# MOSFET_killswitch.net
KiCad netlist of a schematic drawn in Altium Designer
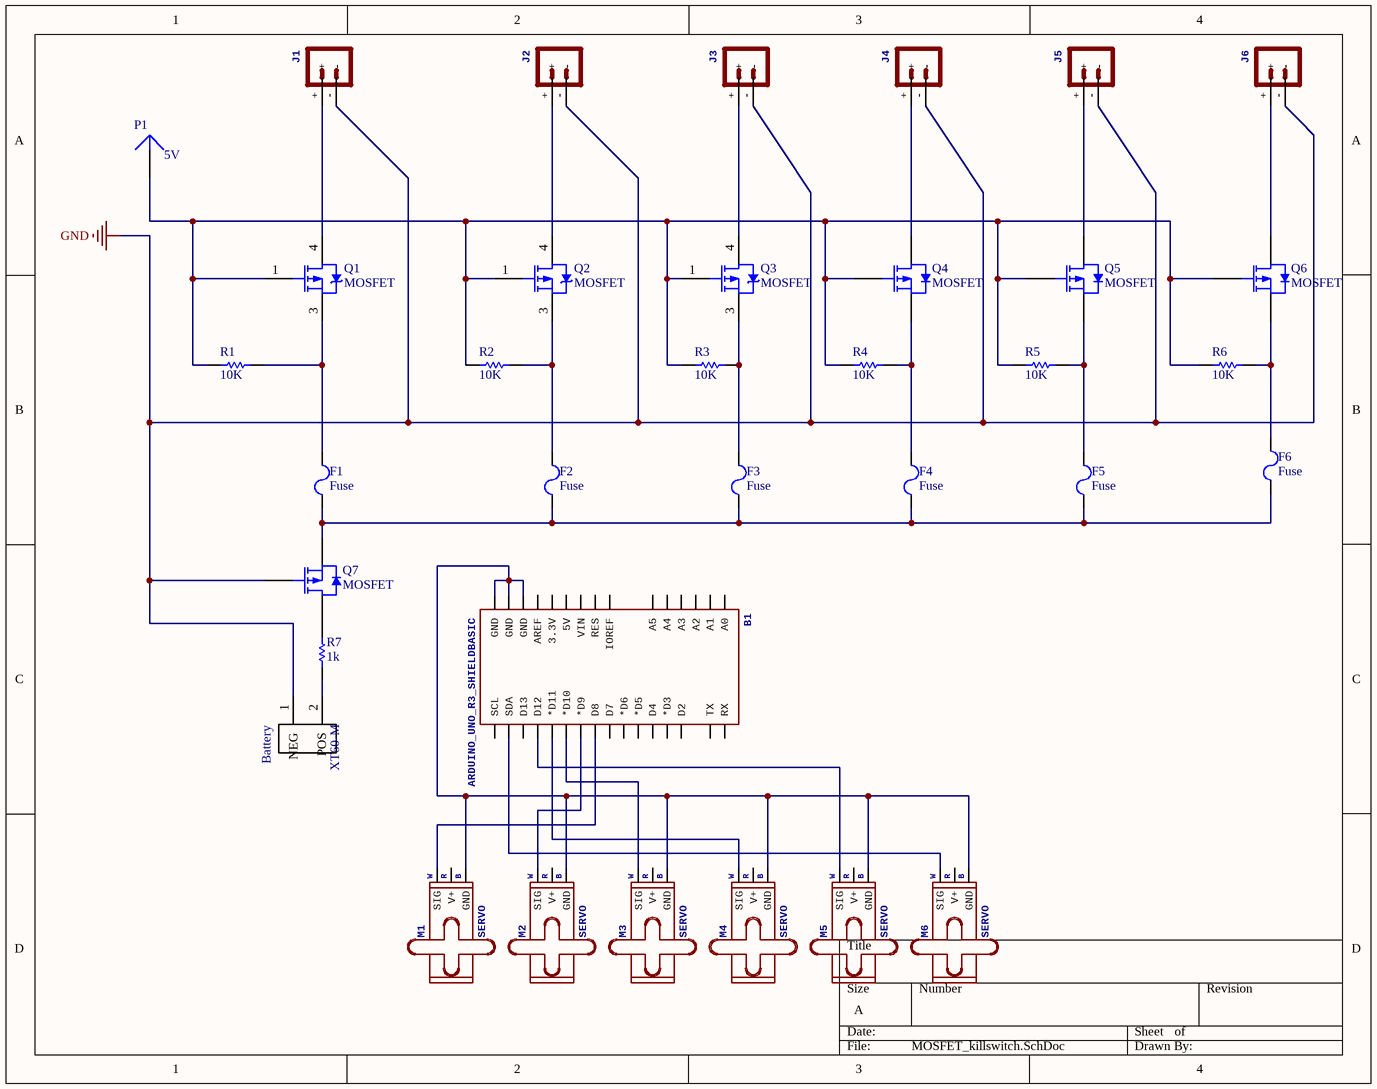
[diagram p0: MOSFET_killswitch.SchDoc]

(export (version "E")
  (design (tool "Eeschema 10.0.6"))
  (components
    (comp (ref "B1")
      (value "ARDUINO_UNO_R3_SHIELDBASIC")
      (footprint "UNO_R3_SHIELD")
      (libsource (lib "SparkFun-Boards") (part "ARDUINO_UNO_R3_SHIELDBASIC"))
    )
    (comp (ref "Battery")
      (value "XT60-M")
      (footprint "*AMASS_XT60-M")
      (fields (field (name "MF") "AMASS"))
      (libsource (lib "XT60-M") (part "XT60-M"))
    )
    (comp (ref "F1")
      (value "Fuse")
      (footprint "LFUS-45X_V")
      (description "Fuse, 65 V, 15 A, -55 to 125 degC, 2-Pin SMD, RoHS, Tape and Reel")
      (fields (field (name "MANUFACTURER") "Littelfuse"))
      (libsource (lib "Altium Content Vault") (part "FUSE-2"))
    )
    (comp (ref "F2")
      (value "Fuse")
      (footprint "LFUS-45X_V")
      (description "Fuse, 65 V, 15 A, -55 to 125 degC, 2-Pin SMD, RoHS, Tape and Reel")
      (fields (field (name "MANUFACTURER") "Littelfuse"))
      (libsource (lib "Altium Content Vault") (part "FUSE-2"))
    )
    (comp (ref "F3")
      (value "Fuse")
      (footprint "LFUS-45X_V")
      (description "Fuse, 65 V, 15 A, -55 to 125 degC, 2-Pin SMD, RoHS, Tape and Reel")
      (fields (field (name "MANUFACTURER") "Littelfuse"))
      (libsource (lib "Altium Content Vault") (part "FUSE-2"))
    )
    (comp (ref "F4")
      (value "Fuse")
      (footprint "LFUS-45X_V")
      (description "Fuse, 65 V, 15 A, -55 to 125 degC, 2-Pin SMD, RoHS, Tape and Reel")
      (fields (field (name "MANUFACTURER") "Littelfuse"))
      (libsource (lib "Altium Content Vault") (part "FUSE-2"))
    )
    (comp (ref "F5")
      (value "Fuse")
      (footprint "LFUS-45X_V")
      (description "Fuse, 65 V, 15 A, -55 to 125 degC, 2-Pin SMD, RoHS, Tape and Reel")
      (fields (field (name "MANUFACTURER") "Littelfuse"))
      (libsource (lib "Altium Content Vault") (part "FUSE-2"))
    )
    (comp (ref "F6")
      (value "Fuse")
      (footprint "LFUS-45X_V")
      (description "Fuse, 65 V, 15 A, -55 to 125 degC, 2-Pin SMD, RoHS, Tape and Reel")
      (fields (field (name "MANUFACTURER") "Littelfuse"))
      (libsource (lib "Altium Content Vault") (part "FUSE-2"))
    )
    (comp (ref "J1")
      (value "BATTERY_CONN_DEANS1")
      (footprint "DEANS")
      (libsource (lib "SparkFun-Connectors") (part "BATTERY_CONN_DEANS"))
    )
    (comp (ref "J2")
      (value "BATTERY_CONN_DEANS")
      (footprint "DEANS")
      (libsource (lib "SparkFun-Connectors") (part "BATTERY_CONN_DEANS"))
    )
    (comp (ref "J3")
      (value "BATTERY_CONN_DEANS")
      (footprint "DEANS")
      (libsource (lib "SparkFun-Connectors") (part "BATTERY_CONN_DEANS"))
    )
    (comp (ref "J4")
      (value "BATTERY_CONN_DEANS")
      (footprint "DEANS")
      (libsource (lib "SparkFun-Connectors") (part "BATTERY_CONN_DEANS"))
    )
    (comp (ref "J5")
      (value "BATTERY_CONN_DEANS")
      (footprint "DEANS")
      (libsource (lib "SparkFun-Connectors") (part "BATTERY_CONN_DEANS"))
    )
    (comp (ref "J6")
      (value "BATTERY_CONN_DEANS")
      (footprint "DEANS")
      (libsource (lib "SparkFun-Connectors") (part "BATTERY_CONN_DEANS"))
    )
    (comp (ref "M1")
      (value "SERVO")
      (footprint "1X03")
      (fields (field (name "W") "W") (field (name "R") "R") (field (name "B") "B"))
      (libsource (lib "SparkFun-Electromechanical") (part "SERVO"))
    )
    (comp (ref "M2")
      (value "SERVO")
      (footprint "1X03")
      (fields (field (name "W") "W") (field (name "R") "R") (field (name "B") "B"))
      (libsource (lib "SparkFun-Electromechanical") (part "SERVO"))
    )
    (comp (ref "M3")
      (value "SERVO")
      (footprint "1X03")
      (fields (field (name "W") "W") (field (name "R") "R") (field (name "B") "B"))
      (libsource (lib "SparkFun-Electromechanical") (part "SERVO"))
    )
    (comp (ref "M4")
      (value "SERVO")
      (footprint "1X03")
      (fields (field (name "W") "W") (field (name "R") "R") (field (name "B") "B"))
      (libsource (lib "SparkFun-Electromechanical") (part "SERVO"))
    )
    (comp (ref "M5")
      (value "SERVO")
      (footprint "1X03")
      (fields (field (name "W") "W") (field (name "R") "R") (field (name "B") "B"))
      (libsource (lib "SparkFun-Electromechanical") (part "SERVO"))
    )
    (comp (ref "M6")
      (value "SERVO")
      (footprint "1X03")
      (fields (field (name "W") "W") (field (name "R") "R") (field (name "B") "B"))
      (libsource (lib "SparkFun-Electromechanical") (part "SERVO"))
    )
    (comp (ref "P1")
      (value "5V")
      (footprint "PIN1")
      (description "Plug")
      (fields (field (name "PUBLISHER") "Altium Limited"))
      (libsource (lib "Miscellaneous Connectors") (part "Plug"))
    )
    (comp (ref "Q1")
      (value "MOSFET")
      (footprint "ONSC-DPAK-3-369C-01_V")
      (description "Power MOSFET -60 V, -15.5 A, Single P-Channel, 3-Pin DPAK, Pb-Free, Tape and Reel")
      (fields (field (name "PARTNUMBER") "NTD20P06LT4G") (field (name "MANUFACTURER") "On Semiconductor"))
      (libsource (lib "Altium Content Vault") (part "ONSC-PMOS-G1S3D4-3_B"))
    )
    (comp (ref "Q2")
      (value "MOSFET")
      (footprint "ONSC-DPAK-3-369C-01_V")
      (description "Power MOSFET -60 V, -15.5 A, Single P-Channel, 3-Pin DPAK, Pb-Free, Tape and Reel")
      (fields (field (name "PARTNUMBER") "NTD20P06LT4G") (field (name "MANUFACTURER") "On Semiconductor"))
      (libsource (lib "Altium Content Vault") (part "ONSC-PMOS-G1S3D4-3_B"))
    )
    (comp (ref "Q3")
      (value "MOSFET")
      (footprint "ONSC-DPAK-3-369C-01_V")
      (description "Power MOSFET -60 V, -15.5 A, Single P-Channel, 3-Pin DPAK, Pb-Free, Tape and Reel")
      (fields (field (name "PARTNUMBER") "NTD20P06LT4G") (field (name "MANUFACTURER") "On Semiconductor"))
      (libsource (lib "Altium Content Vault") (part "ONSC-PMOS-G1S3D4-3_B"))
    )
    (comp (ref "Q4")
      (value "MOSFET")
      (footprint "VISH-SI2323DS-T1-E3-3_V")
      (description "P-Channel MOSFET, 20 V, -55 to 150 degC, 3-Pin TO-236, RoHS, Tape and Reel")
      (fields (field (name "MANUFACTURER") "Vishay"))
      (libsource (lib "Altium Content Vault") (part "VISH-SI2323DS-T1-E3-3"))
    )
    (comp (ref "Q5")
      (value "MOSFET")
      (footprint "VISH-SI2323DS-T1-E3-3_V")
      (description "P-Channel MOSFET, 20 V, -55 to 150 degC, 3-Pin TO-236, RoHS, Tape and Reel")
      (fields (field (name "MANUFACTURER") "Vishay"))
      (libsource (lib "Altium Content Vault") (part "VISH-SI2323DS-T1-E3-3"))
    )
    (comp (ref "Q6")
      (value "MOSFET")
      (footprint "VISH-SI2323DS-T1-E3-3_V")
      (description "P-Channel MOSFET, 20 V, -55 to 150 degC, 3-Pin TO-236, RoHS, Tape and Reel")
      (fields (field (name "MANUFACTURER") "Vishay"))
      (libsource (lib "Altium Content Vault") (part "VISH-SI2323DS-T1-E3-3"))
    )
    (comp (ref "Q7")
      (value "MOSFET")
      (footprint "VISH-SI2323DS-T1-E3-3_V")
      (description "P-Channel MOSFET, 20 V, -55 to 150 degC, 3-Pin TO-236, RoHS, Tape and Reel")
      (fields (field (name "MANUFACTURER") "Vishay"))
      (libsource (lib "Altium Content Vault") (part "VISH-SI2323DS-T1-E3-3"))
    )
    (comp (ref "R1")
      (value "10K")
      (footprint "RESC1609X55X30NL10T20")
      (fields (field (name "MANUFACTURER") "Vishay Dale") (field (name "PART NUMBER") "TNPW060310K0BEEA"))
      (libsource (lib "Altium Content Vault") (part "RES"))
    )
    (comp (ref "R2")
      (value "10K")
      (footprint "RESC1609X55X30NL10T20")
      (fields (field (name "MANUFACTURER") "Vishay Dale") (field (name "PART NUMBER") "TNPW060310K0BEEA"))
      (libsource (lib "Altium Content Vault") (part "RES"))
    )
    (comp (ref "R3")
      (value "10K")
      (footprint "RESC1609X55X30NL10T20")
      (fields (field (name "MANUFACTURER") "Vishay Dale") (field (name "PART NUMBER") "TNPW060310K0BEEA"))
      (libsource (lib "Altium Content Vault") (part "RES"))
    )
    (comp (ref "R4")
      (value "10K")
      (footprint "RESC1609X55X30NL10T20")
      (fields (field (name "MANUFACTURER") "Vishay Dale") (field (name "PART NUMBER") "TNPW060310K0BEEA"))
      (libsource (lib "Altium Content Vault") (part "RES"))
    )
    (comp (ref "R5")
      (value "10K")
      (footprint "RESC1609X55X30NL10T20")
      (fields (field (name "MANUFACTURER") "Vishay Dale") (field (name "PART NUMBER") "TNPW060310K0BEEA"))
      (libsource (lib "Altium Content Vault") (part "RES"))
    )
    (comp (ref "R6")
      (value "10K")
      (footprint "RESC1609X55X30NL10T20")
      (fields (field (name "MANUFACTURER") "Vishay Dale") (field (name "PART NUMBER") "TNPW060310K0BEEA"))
      (libsource (lib "Altium Content Vault") (part "RES"))
    )
    (comp (ref "R7")
      (value "1k")
      (footprint "RESC2013X50X30ML20T20")
      (fields (field (name "PART NUMBER") "CRCW08051K00JNTA") (field (name "MANUFACTURER") "Vishay Dale"))
      (libsource (lib "Altium Content Vault") (part "RES"))
    )
  )
  (nets
    (net (code "1") (name "GND") (class "Default")
      (node (ref "Battery") (pin "1") (pinfunction "NEG_1") (pintype "passive"))
      (node (ref "J1") (pin "-") (pinfunction "-_-") (pintype "passive"))
      (node (ref "J2") (pin "-") (pinfunction "-_-") (pintype "passive"))
      (node (ref "J3") (pin "-") (pinfunction "-_-") (pintype "passive"))
      (node (ref "J4") (pin "-") (pinfunction "-_-") (pintype "passive"))
      (node (ref "J5") (pin "-") (pinfunction "-_-") (pintype "passive"))
      (node (ref "J6") (pin "-") (pinfunction "-_-") (pintype "passive"))
      (node (ref "Q7") (pin "1") (pinfunction "G_1") (pintype "passive"))
    )
    (net (code "2") (name "Net-(B1-*D9)") (class "Default")
      (node (ref "B1") (pin "D9") (pinfunction "*D9_D9") (pintype "bidirectional"))
      (node (ref "M2") (pin "1") (pinfunction "SIG_1") (pintype "bidirectional"))
    )
    (net (code "3") (name "Net-(B1-*D10)") (class "Default")
      (node (ref "B1") (pin "D10") (pinfunction "*D10_D10") (pintype "bidirectional"))
      (node (ref "M3") (pin "1") (pinfunction "SIG_1") (pintype "bidirectional"))
    )
    (net (code "4") (name "Net-(B1-*D11)") (class "Default")
      (node (ref "B1") (pin "D11") (pinfunction "*D11_D11") (pintype "bidirectional"))
      (node (ref "M4") (pin "1") (pinfunction "SIG_1") (pintype "bidirectional"))
    )
    (net (code "5") (name "Net-(Battery-POS)") (class "Default")
      (node (ref "Battery") (pin "2") (pinfunction "POS_2") (pintype "passive"))
      (node (ref "R7") (pin "1") (pinfunction "1_1") (pintype "passive"))
    )
    (net (code "6") (name "Net-(M1-GND)") (class "Default")
      (node (ref "B1") (pin "GND@0") (pinfunction "GND_GND@0") (pintype "bidirectional"))
      (node (ref "B1") (pin "GND@1") (pinfunction "GND_GND@1") (pintype "bidirectional"))
      (node (ref "B1") (pin "GND@2") (pinfunction "GND_GND@2") (pintype "bidirectional"))
      (node (ref "M1") (pin "3") (pinfunction "GND_3") (pintype "bidirectional"))
      (node (ref "M2") (pin "3") (pinfunction "GND_3") (pintype "bidirectional"))
      (node (ref "M3") (pin "3") (pinfunction "GND_3") (pintype "bidirectional"))
      (node (ref "M4") (pin "3") (pinfunction "GND_3") (pintype "bidirectional"))
      (node (ref "M5") (pin "3") (pinfunction "GND_3") (pintype "bidirectional"))
      (node (ref "M6") (pin "3") (pinfunction "GND_3") (pintype "bidirectional"))
    )
    (net (code "7") (name "Net-(M1-SIG)") (class "Default")
      (node (ref "B1") (pin "D8") (pinfunction "D8_D8") (pintype "bidirectional"))
      (node (ref "M1") (pin "1") (pinfunction "SIG_1") (pintype "bidirectional"))
    )
    (net (code "8") (name "Net-(M5-SIG)") (class "Default")
      (node (ref "B1") (pin "D12") (pinfunction "D12_D12") (pintype "bidirectional"))
      (node (ref "M5") (pin "1") (pinfunction "SIG_1") (pintype "bidirectional"))
    )
    (net (code "9") (name "Net-(M6-SIG)") (class "Default")
      (node (ref "B1") (pin "SDA") (pinfunction "SDA_SDA") (pintype "bidirectional"))
      (node (ref "M6") (pin "1") (pinfunction "SIG_1") (pintype "bidirectional"))
    )
    (net (code "10") (name "Net-(Q1-D)") (class "Default")
      (node (ref "J1") (pin "+") (pinfunction "+_+") (pintype "passive"))
      (node (ref "Q1") (pin "4") (pinfunction "D_4") (pintype "passive"))
    )
    (net (code "11") (name "Net-(Q1-G)") (class "Default")
      (node (ref "P1") (pin "1") (pinfunction "1_1") (pintype "passive"))
      (node (ref "Q1") (pin "1") (pinfunction "G_1") (pintype "passive"))
      (node (ref "Q2") (pin "1") (pinfunction "G_1") (pintype "passive"))
      (node (ref "Q3") (pin "1") (pinfunction "G_1") (pintype "passive"))
      (node (ref "Q4") (pin "1") (pinfunction "G_1") (pintype "passive"))
      (node (ref "Q5") (pin "1") (pinfunction "G_1") (pintype "passive"))
      (node (ref "Q6") (pin "1") (pinfunction "G_1") (pintype "passive"))
      (node (ref "R1") (pin "1") (pinfunction "1_1") (pintype "passive"))
      (node (ref "R2") (pin "1") (pinfunction "1_1") (pintype "passive"))
      (node (ref "R3") (pin "1") (pinfunction "1_1") (pintype "passive"))
      (node (ref "R4") (pin "1") (pinfunction "1_1") (pintype "passive"))
      (node (ref "R5") (pin "1") (pinfunction "1_1") (pintype "passive"))
      (node (ref "R6") (pin "1") (pinfunction "1_1") (pintype "passive"))
    )
    (net (code "12") (name "Net-(Q1-S)") (class "Default")
      (node (ref "F1") (pin "2") (pinfunction "2_2") (pintype "passive"))
      (node (ref "Q1") (pin "3") (pinfunction "S_3") (pintype "passive"))
      (node (ref "R1") (pin "2") (pinfunction "2_2") (pintype "passive"))
    )
    (net (code "13") (name "Net-(Q2-D)") (class "Default")
      (node (ref "J2") (pin "+") (pinfunction "+_+") (pintype "passive"))
      (node (ref "Q2") (pin "4") (pinfunction "D_4") (pintype "passive"))
    )
    (net (code "14") (name "Net-(Q2-S)") (class "Default")
      (node (ref "F2") (pin "2") (pinfunction "2_2") (pintype "passive"))
      (node (ref "Q2") (pin "3") (pinfunction "S_3") (pintype "passive"))
      (node (ref "R2") (pin "2") (pinfunction "2_2") (pintype "passive"))
    )
    (net (code "15") (name "Net-(Q3-D)") (class "Default")
      (node (ref "J3") (pin "+") (pinfunction "+_+") (pintype "passive"))
      (node (ref "Q3") (pin "4") (pinfunction "D_4") (pintype "passive"))
    )
    (net (code "16") (name "Net-(Q3-S)") (class "Default")
      (node (ref "F3") (pin "2") (pinfunction "2_2") (pintype "passive"))
      (node (ref "Q3") (pin "3") (pinfunction "S_3") (pintype "passive"))
      (node (ref "R3") (pin "2") (pinfunction "2_2") (pintype "passive"))
    )
    (net (code "17") (name "Net-(Q4-D)") (class "Default")
      (node (ref "J4") (pin "+") (pinfunction "+_+") (pintype "passive"))
      (node (ref "Q4") (pin "3") (pinfunction "D_3") (pintype "passive"))
    )
    (net (code "18") (name "Net-(Q4-S)") (class "Default")
      (node (ref "F4") (pin "2") (pinfunction "2_2") (pintype "passive"))
      (node (ref "Q4") (pin "2") (pinfunction "S_2") (pintype "passive"))
      (node (ref "R4") (pin "2") (pinfunction "2_2") (pintype "passive"))
    )
    (net (code "19") (name "Net-(Q5-D)") (class "Default")
      (node (ref "J5") (pin "+") (pinfunction "+_+") (pintype "passive"))
      (node (ref "Q5") (pin "3") (pinfunction "D_3") (pintype "passive"))
    )
    (net (code "20") (name "Net-(Q5-S)") (class "Default")
      (node (ref "F5") (pin "2") (pinfunction "2_2") (pintype "passive"))
      (node (ref "Q5") (pin "2") (pinfunction "S_2") (pintype "passive"))
      (node (ref "R5") (pin "2") (pinfunction "2_2") (pintype "passive"))
    )
    (net (code "21") (name "Net-(Q6-D)") (class "Default")
      (node (ref "J6") (pin "+") (pinfunction "+_+") (pintype "passive"))
      (node (ref "Q6") (pin "3") (pinfunction "D_3") (pintype "passive"))
    )
    (net (code "22") (name "Net-(Q6-S)") (class "Default")
      (node (ref "F6") (pin "2") (pinfunction "2_2") (pintype "passive"))
      (node (ref "Q6") (pin "2") (pinfunction "S_2") (pintype "passive"))
      (node (ref "R6") (pin "2") (pinfunction "2_2") (pintype "passive"))
    )
    (net (code "23") (name "Net-(Q7-D)") (class "Default")
      (node (ref "Q7") (pin "3") (pinfunction "D_3") (pintype "passive"))
      (node (ref "R7") (pin "2") (pinfunction "2_2") (pintype "passive"))
    )
    (net (code "24") (name "Net-(Q7-S)") (class "Default")
      (node (ref "F1") (pin "1") (pinfunction "1_1") (pintype "passive"))
      (node (ref "F2") (pin "1") (pinfunction "1_1") (pintype "passive"))
      (node (ref "F3") (pin "1") (pinfunction "1_1") (pintype "passive"))
      (node (ref "F4") (pin "1") (pinfunction "1_1") (pintype "passive"))
      (node (ref "F5") (pin "1") (pinfunction "1_1") (pintype "passive"))
      (node (ref "F6") (pin "1") (pinfunction "1_1") (pintype "passive"))
      (node (ref "Q7") (pin "2") (pinfunction "S_2") (pintype "passive"))
    )
    (net (code "25") (name "unconnected-(B1-*D3-PadD3)") (class "Default")
      (node (ref "B1") (pin "D3") (pinfunction "*D3_D3") (pintype "bidirectional"))
    )
    (net (code "26") (name "unconnected-(B1-*D5-PadD5)") (class "Default")
      (node (ref "B1") (pin "D5") (pinfunction "*D5_D5") (pintype "bidirectional"))
    )
    (net (code "27") (name "unconnected-(B1-*D6-PadD6)") (class "Default")
      (node (ref "B1") (pin "D6") (pinfunction "*D6_D6") (pintype "bidirectional"))
    )
    (net (code "28") (name "unconnected-(B1-Pad3.3V)") (class "Default")
      (node (ref "B1") (pin "3.3V") (pinfunction "3.3V_3.3V") (pintype "bidirectional"))
    )
    (net (code "29") (name "unconnected-(B1-Pad5V)") (class "Default")
      (node (ref "B1") (pin "5V") (pinfunction "5V_5V") (pintype "bidirectional"))
    )
    (net (code "30") (name "unconnected-(B1-PadA0)") (class "Default")
      (node (ref "B1") (pin "A0") (pinfunction "A0_A0") (pintype "bidirectional"))
    )
    (net (code "31") (name "unconnected-(B1-PadA1)") (class "Default")
      (node (ref "B1") (pin "A1") (pinfunction "A1_A1") (pintype "bidirectional"))
    )
    (net (code "32") (name "unconnected-(B1-PadA2)") (class "Default")
      (node (ref "B1") (pin "A2") (pinfunction "A2_A2") (pintype "bidirectional"))
    )
    (net (code "33") (name "unconnected-(B1-PadA3)") (class "Default")
      (node (ref "B1") (pin "A3") (pinfunction "A3_A3") (pintype "bidirectional"))
    )
    (net (code "34") (name "unconnected-(B1-PadA4)") (class "Default")
      (node (ref "B1") (pin "A4") (pinfunction "A4_A4") (pintype "bidirectional"))
    )
    (net (code "35") (name "unconnected-(B1-PadA5)") (class "Default")
      (node (ref "B1") (pin "A5") (pinfunction "A5_A5") (pintype "bidirectional"))
    )
    (net (code "36") (name "unconnected-(B1-PadAREF)") (class "Default")
      (node (ref "B1") (pin "AREF") (pinfunction "AREF_AREF") (pintype "bidirectional"))
    )
    (net (code "37") (name "unconnected-(B1-PadD2)") (class "Default")
      (node (ref "B1") (pin "D2") (pinfunction "D2_D2") (pintype "bidirectional"))
    )
    (net (code "38") (name "unconnected-(B1-PadD4)") (class "Default")
      (node (ref "B1") (pin "D4") (pinfunction "D4_D4") (pintype "bidirectional"))
    )
    (net (code "39") (name "unconnected-(B1-PadD7)") (class "Default")
      (node (ref "B1") (pin "D7") (pinfunction "D7_D7") (pintype "bidirectional"))
    )
    (net (code "40") (name "unconnected-(B1-PadD13)") (class "Default")
      (node (ref "B1") (pin "D13") (pinfunction "D13_D13") (pintype "bidirectional"))
    )
    (net (code "41") (name "unconnected-(B1-PadIOREF)") (class "Default")
      (node (ref "B1") (pin "IOREF") (pinfunction "IOREF_IOREF") (pintype "bidirectional"))
    )
    (net (code "42") (name "unconnected-(B1-PadRES)") (class "Default")
      (node (ref "B1") (pin "RES") (pinfunction "RES_RES") (pintype "bidirectional"))
    )
    (net (code "43") (name "unconnected-(B1-PadRX)") (class "Default")
      (node (ref "B1") (pin "RX") (pinfunction "RX_RX") (pintype "bidirectional"))
    )
    (net (code "44") (name "unconnected-(B1-PadSCL)") (class "Default")
      (node (ref "B1") (pin "SCL") (pinfunction "SCL_SCL") (pintype "bidirectional"))
    )
    (net (code "45") (name "unconnected-(B1-PadTX)") (class "Default")
      (node (ref "B1") (pin "TX") (pinfunction "TX_TX") (pintype "bidirectional"))
    )
    (net (code "46") (name "unconnected-(B1-PadVIN)") (class "Default")
      (node (ref "B1") (pin "VIN") (pinfunction "VIN_VIN") (pintype "bidirectional"))
    )
    (net (code "47") (name "unconnected-(M1-V+-Pad2)") (class "Default")
      (node (ref "M1") (pin "2") (pinfunction "V+_2") (pintype "bidirectional"))
    )
    (net (code "48") (name "unconnected-(M2-V+-Pad2)") (class "Default")
      (node (ref "M2") (pin "2") (pinfunction "V+_2") (pintype "bidirectional"))
    )
    (net (code "49") (name "unconnected-(M3-V+-Pad2)") (class "Default")
      (node (ref "M3") (pin "2") (pinfunction "V+_2") (pintype "bidirectional"))
    )
    (net (code "50") (name "unconnected-(M4-V+-Pad2)") (class "Default")
      (node (ref "M4") (pin "2") (pinfunction "V+_2") (pintype "bidirectional"))
    )
    (net (code "51") (name "unconnected-(M5-V+-Pad2)") (class "Default")
      (node (ref "M5") (pin "2") (pinfunction "V+_2") (pintype "bidirectional"))
    )
    (net (code "52") (name "unconnected-(M6-V+-Pad2)") (class "Default")
      (node (ref "M6") (pin "2") (pinfunction "V+_2") (pintype "bidirectional"))
    )
  )
)
